# MPU6050_ledMatrix.net
KiCad netlist of a schematic drawn in Altium Designer
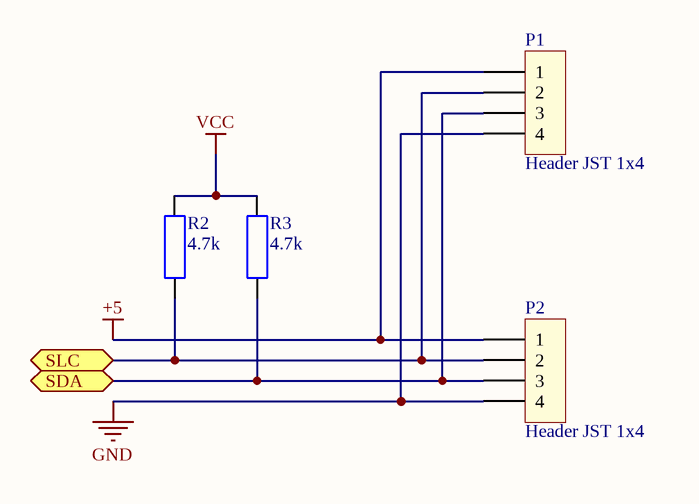
[diagram p0: MPU6050_ledMatrix.SchDoc]

(export (version "E")
  (design (tool "Eeschema 10.0.6"))
  (components
    (comp (ref "P1")
      (value "Header JST 1x4")
      (footprint "THT_HEADER_78MIL_JST_1X4_MALE")
      (libsource (lib "VPP_Library") (part "Header_JST_1x4"))
    )
    (comp (ref "P2")
      (value "Header JST 1x4")
      (footprint "THT_HEADER_78MIL_JST_1X4_MALE")
      (libsource (lib "VPP_Library") (part "Header_JST_1x4"))
    )
    (comp (ref "R2")
      (value "4.7k")
      (footprint "SMD_RESISTOR_1206")
      (description "Resistor")
      (libsource (lib "VPP_Library") (part "Resistor"))
    )
    (comp (ref "R3")
      (value "4.7k")
      (footprint "SMD_RESISTOR_1206")
      (description "Resistor")
      (libsource (lib "VPP_Library") (part "Resistor"))
    )
  )
  (nets
    (net (code "1") (name "+5") (class "Default")
      (node (ref "P1") (pin "1") (pinfunction "1_1") (pintype "passive"))
      (node (ref "P2") (pin "1") (pinfunction "1_1") (pintype "passive"))
    )
    (net (code "2") (name "/SDA") (class "Default")
      (node (ref "P1") (pin "3") (pinfunction "3_3") (pintype "passive"))
      (node (ref "P2") (pin "3") (pinfunction "3_3") (pintype "passive"))
      (node (ref "R3") (pin "2") (pinfunction "2_2") (pintype "passive"))
    )
    (net (code "3") (name "/SLC") (class "Default")
      (node (ref "P1") (pin "2") (pinfunction "2_2") (pintype "passive"))
      (node (ref "P2") (pin "2") (pinfunction "2_2") (pintype "passive"))
      (node (ref "R2") (pin "2") (pinfunction "2_2") (pintype "passive"))
    )
    (net (code "4") (name "GND") (class "Default")
      (node (ref "P1") (pin "4") (pinfunction "4_4") (pintype "passive"))
      (node (ref "P2") (pin "4") (pinfunction "4_4") (pintype "passive"))
    )
    (net (code "5") (name "VCC") (class "Default")
      (node (ref "R2") (pin "1") (pinfunction "1_1") (pintype "passive"))
      (node (ref "R3") (pin "1") (pinfunction "1_1") (pintype "passive"))
    )
  )
)
